# bombhonor.net
KiCad netlist of a schematic drawn in EAGLE
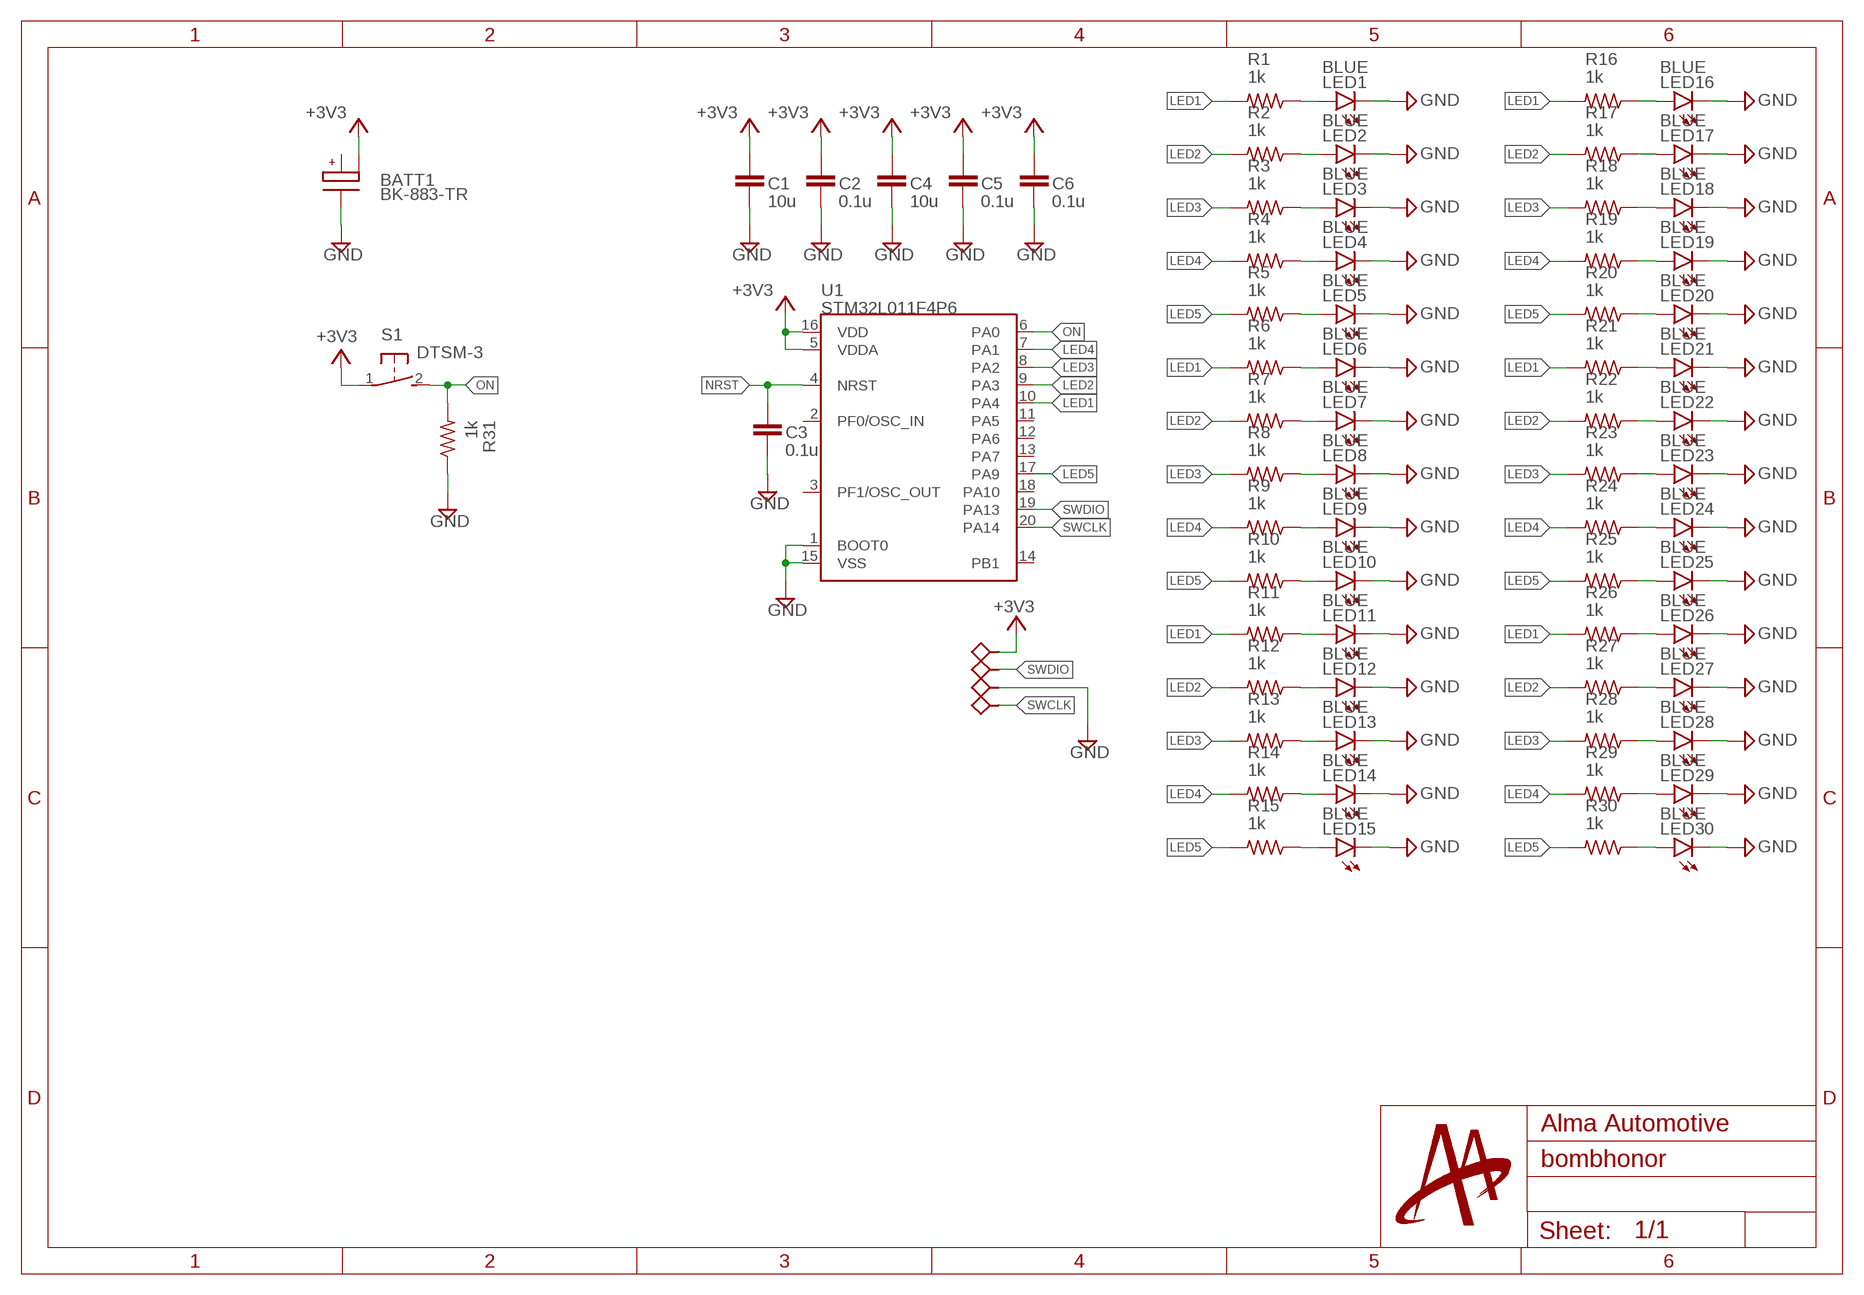
[diagram p0: schematic, sheet 1]

(export (version "E")
  (design (tool "Eeschema 10.0.6"))
  (components
    (comp (ref "BATT1")
      (value "BK-883-TR")
      (footprint "eagle-import:BK-883-TR")
      (libsource (lib "eagle-import") (part "BK-883-TR"))
    )
    (comp (ref "C1")
      (value "10u")
      (footprint "eagle-import:0805[2012]")
      (fields (field (name "PARTNO") "CL21A106KQCLRNC"))
      (libsource (lib "eagle-import") (part "C0805"))
    )
    (comp (ref "C2")
      (value "0.1u")
      (footprint "eagle-import:0603[1608]")
      (fields (field (name "PARTNO") "CL10B104KB8NNNC"))
      (libsource (lib "eagle-import") (part "C0603"))
    )
    (comp (ref "C3")
      (value "0.1u")
      (footprint "eagle-import:0603[1608]")
      (fields (field (name "PARTNO") "CL10B104KB8NNNC"))
      (libsource (lib "eagle-import") (part "C0603"))
    )
    (comp (ref "C4")
      (value "10u")
      (footprint "eagle-import:0805[2012]")
      (fields (field (name "PARTNO") "CL21A106KQCLRNC"))
      (libsource (lib "eagle-import") (part "C0805"))
    )
    (comp (ref "C5")
      (value "0.1u")
      (footprint "eagle-import:0603[1608]")
      (fields (field (name "PARTNO") "CL10B104KB8NNNC"))
      (libsource (lib "eagle-import") (part "C0603"))
    )
    (comp (ref "C6")
      (value "0.1u")
      (footprint "eagle-import:0603[1608]")
      (fields (field (name "PARTNO") "CL10B104KB8NNNC"))
      (libsource (lib "eagle-import") (part "C0603"))
    )
    (comp (ref "LED1")
      (value "BLUE")
      (footprint "eagle-import:1206[3216]BOTTOM_ENTRY")
      (fields (field (name "PARTNO") "LTST-C230TBKT"))
      (libsource (lib "eagle-import") (part "LED_SMD1206"))
    )
    (comp (ref "LED2")
      (value "BLUE")
      (footprint "eagle-import:1206[3216]BOTTOM_ENTRY")
      (fields (field (name "PARTNO") "LTST-C230TBKT"))
      (libsource (lib "eagle-import") (part "LED_SMD1206"))
    )
    (comp (ref "LED3")
      (value "BLUE")
      (footprint "eagle-import:1206[3216]BOTTOM_ENTRY")
      (fields (field (name "PARTNO") "LTST-C230TBKT"))
      (libsource (lib "eagle-import") (part "LED_SMD1206"))
    )
    (comp (ref "LED4")
      (value "BLUE")
      (footprint "eagle-import:1206[3216]BOTTOM_ENTRY")
      (fields (field (name "PARTNO") "LTST-C230TBKT"))
      (libsource (lib "eagle-import") (part "LED_SMD1206"))
    )
    (comp (ref "LED5")
      (value "BLUE")
      (footprint "eagle-import:1206[3216]BOTTOM_ENTRY")
      (fields (field (name "PARTNO") "LTST-C230TBKT"))
      (libsource (lib "eagle-import") (part "LED_SMD1206"))
    )
    (comp (ref "LED6")
      (value "BLUE")
      (footprint "eagle-import:1206[3216]BOTTOM_ENTRY")
      (fields (field (name "PARTNO") "LTST-C230TBKT"))
      (libsource (lib "eagle-import") (part "LED_SMD1206"))
    )
    (comp (ref "LED7")
      (value "BLUE")
      (footprint "eagle-import:1206[3216]BOTTOM_ENTRY")
      (fields (field (name "PARTNO") "LTST-C230TBKT"))
      (libsource (lib "eagle-import") (part "LED_SMD1206"))
    )
    (comp (ref "LED8")
      (value "BLUE")
      (footprint "eagle-import:1206[3216]BOTTOM_ENTRY")
      (fields (field (name "PARTNO") "LTST-C230TBKT"))
      (libsource (lib "eagle-import") (part "LED_SMD1206"))
    )
    (comp (ref "LED9")
      (value "BLUE")
      (footprint "eagle-import:1206[3216]BOTTOM_ENTRY")
      (fields (field (name "PARTNO") "LTST-C230TBKT"))
      (libsource (lib "eagle-import") (part "LED_SMD1206"))
    )
    (comp (ref "LED10")
      (value "BLUE")
      (footprint "eagle-import:1206[3216]BOTTOM_ENTRY")
      (fields (field (name "PARTNO") "LTST-C230TBKT"))
      (libsource (lib "eagle-import") (part "LED_SMD1206"))
    )
    (comp (ref "LED11")
      (value "BLUE")
      (footprint "eagle-import:1206[3216]BOTTOM_ENTRY")
      (fields (field (name "PARTNO") "LTST-C230TBKT"))
      (libsource (lib "eagle-import") (part "LED_SMD1206"))
    )
    (comp (ref "LED12")
      (value "BLUE")
      (footprint "eagle-import:1206[3216]BOTTOM_ENTRY")
      (fields (field (name "PARTNO") "LTST-C230TBKT"))
      (libsource (lib "eagle-import") (part "LED_SMD1206"))
    )
    (comp (ref "LED13")
      (value "BLUE")
      (footprint "eagle-import:1206[3216]BOTTOM_ENTRY")
      (fields (field (name "PARTNO") "LTST-C230TBKT"))
      (libsource (lib "eagle-import") (part "LED_SMD1206"))
    )
    (comp (ref "LED14")
      (value "BLUE")
      (footprint "eagle-import:1206[3216]BOTTOM_ENTRY")
      (fields (field (name "PARTNO") "LTST-C230TBKT"))
      (libsource (lib "eagle-import") (part "LED_SMD1206"))
    )
    (comp (ref "LED15")
      (value "BLUE")
      (footprint "eagle-import:1206[3216]BOTTOM_ENTRY")
      (fields (field (name "PARTNO") "LTST-C230TBKT"))
      (libsource (lib "eagle-import") (part "LED_SMD1206"))
    )
    (comp (ref "LED16")
      (value "BLUE")
      (footprint "eagle-import:1206[3216]BOTTOM_ENTRY")
      (fields (field (name "PARTNO") "LTST-C230TBKT"))
      (libsource (lib "eagle-import") (part "LED_SMD1206"))
    )
    (comp (ref "LED17")
      (value "BLUE")
      (footprint "eagle-import:1206[3216]BOTTOM_ENTRY")
      (fields (field (name "PARTNO") "LTST-C230TBKT"))
      (libsource (lib "eagle-import") (part "LED_SMD1206"))
    )
    (comp (ref "LED18")
      (value "BLUE")
      (footprint "eagle-import:1206[3216]BOTTOM_ENTRY")
      (fields (field (name "PARTNO") "LTST-C230TBKT"))
      (libsource (lib "eagle-import") (part "LED_SMD1206"))
    )
    (comp (ref "LED19")
      (value "BLUE")
      (footprint "eagle-import:1206[3216]BOTTOM_ENTRY")
      (fields (field (name "PARTNO") "LTST-C230TBKT"))
      (libsource (lib "eagle-import") (part "LED_SMD1206"))
    )
    (comp (ref "LED20")
      (value "BLUE")
      (footprint "eagle-import:1206[3216]BOTTOM_ENTRY")
      (fields (field (name "PARTNO") "LTST-C230TBKT"))
      (libsource (lib "eagle-import") (part "LED_SMD1206"))
    )
    (comp (ref "LED21")
      (value "BLUE")
      (footprint "eagle-import:1206[3216]BOTTOM_ENTRY")
      (fields (field (name "PARTNO") "LTST-C230TBKT"))
      (libsource (lib "eagle-import") (part "LED_SMD1206"))
    )
    (comp (ref "LED22")
      (value "BLUE")
      (footprint "eagle-import:1206[3216]BOTTOM_ENTRY")
      (fields (field (name "PARTNO") "LTST-C230TBKT"))
      (libsource (lib "eagle-import") (part "LED_SMD1206"))
    )
    (comp (ref "LED23")
      (value "BLUE")
      (footprint "eagle-import:1206[3216]BOTTOM_ENTRY")
      (fields (field (name "PARTNO") "LTST-C230TBKT"))
      (libsource (lib "eagle-import") (part "LED_SMD1206"))
    )
    (comp (ref "LED24")
      (value "BLUE")
      (footprint "eagle-import:1206[3216]BOTTOM_ENTRY")
      (fields (field (name "PARTNO") "LTST-C230TBKT"))
      (libsource (lib "eagle-import") (part "LED_SMD1206"))
    )
    (comp (ref "LED25")
      (value "BLUE")
      (footprint "eagle-import:1206[3216]BOTTOM_ENTRY")
      (fields (field (name "PARTNO") "LTST-C230TBKT"))
      (libsource (lib "eagle-import") (part "LED_SMD1206"))
    )
    (comp (ref "LED26")
      (value "BLUE")
      (footprint "eagle-import:1206[3216]BOTTOM_ENTRY")
      (fields (field (name "PARTNO") "LTST-C230TBKT"))
      (libsource (lib "eagle-import") (part "LED_SMD1206"))
    )
    (comp (ref "LED27")
      (value "BLUE")
      (footprint "eagle-import:1206[3216]BOTTOM_ENTRY")
      (fields (field (name "PARTNO") "LTST-C230TBKT"))
      (libsource (lib "eagle-import") (part "LED_SMD1206"))
    )
    (comp (ref "LED28")
      (value "BLUE")
      (footprint "eagle-import:1206[3216]BOTTOM_ENTRY")
      (fields (field (name "PARTNO") "LTST-C230TBKT"))
      (libsource (lib "eagle-import") (part "LED_SMD1206"))
    )
    (comp (ref "LED29")
      (value "BLUE")
      (footprint "eagle-import:1206[3216]BOTTOM_ENTRY")
      (fields (field (name "PARTNO") "LTST-C230TBKT"))
      (libsource (lib "eagle-import") (part "LED_SMD1206"))
    )
    (comp (ref "LED30")
      (value "BLUE")
      (footprint "eagle-import:1206[3216]BOTTOM_ENTRY")
      (fields (field (name "PARTNO") "LTST-C230TBKT"))
      (libsource (lib "eagle-import") (part "LED_SMD1206"))
    )
    (comp (ref "R1")
      (value "1k")
      (footprint "eagle-import:0603[1608]")
      (fields (field (name "PARTNO") "RMCF0603JT1K00"))
      (libsource (lib "eagle-import") (part "R0603"))
    )
    (comp (ref "R2")
      (value "1k")
      (footprint "eagle-import:0603[1608]")
      (fields (field (name "PARTNO") "RMCF0603JT1K00"))
      (libsource (lib "eagle-import") (part "R0603"))
    )
    (comp (ref "R3")
      (value "1k")
      (footprint "eagle-import:0603[1608]")
      (fields (field (name "PARTNO") "RMCF0603JT1K00"))
      (libsource (lib "eagle-import") (part "R0603"))
    )
    (comp (ref "R4")
      (value "1k")
      (footprint "eagle-import:0603[1608]")
      (fields (field (name "PARTNO") "RMCF0603JT1K00"))
      (libsource (lib "eagle-import") (part "R0603"))
    )
    (comp (ref "R5")
      (value "1k")
      (footprint "eagle-import:0603[1608]")
      (fields (field (name "PARTNO") "RMCF0603JT1K00"))
      (libsource (lib "eagle-import") (part "R0603"))
    )
    (comp (ref "R6")
      (value "1k")
      (footprint "eagle-import:0603[1608]")
      (fields (field (name "PARTNO") "RMCF0603JT1K00"))
      (libsource (lib "eagle-import") (part "R0603"))
    )
    (comp (ref "R7")
      (value "1k")
      (footprint "eagle-import:0603[1608]")
      (fields (field (name "PARTNO") "RMCF0603JT1K00"))
      (libsource (lib "eagle-import") (part "R0603"))
    )
    (comp (ref "R8")
      (value "1k")
      (footprint "eagle-import:0603[1608]")
      (fields (field (name "PARTNO") "RMCF0603JT1K00"))
      (libsource (lib "eagle-import") (part "R0603"))
    )
    (comp (ref "R9")
      (value "1k")
      (footprint "eagle-import:0603[1608]")
      (fields (field (name "PARTNO") "RMCF0603JT1K00"))
      (libsource (lib "eagle-import") (part "R0603"))
    )
    (comp (ref "R10")
      (value "1k")
      (footprint "eagle-import:0603[1608]")
      (fields (field (name "PARTNO") "RMCF0603JT1K00"))
      (libsource (lib "eagle-import") (part "R0603"))
    )
    (comp (ref "R11")
      (value "1k")
      (footprint "eagle-import:0603[1608]")
      (fields (field (name "PARTNO") "RMCF0603JT1K00"))
      (libsource (lib "eagle-import") (part "R0603"))
    )
    (comp (ref "R12")
      (value "1k")
      (footprint "eagle-import:0603[1608]")
      (fields (field (name "PARTNO") "RMCF0603JT1K00"))
      (libsource (lib "eagle-import") (part "R0603"))
    )
    (comp (ref "R13")
      (value "1k")
      (footprint "eagle-import:0603[1608]")
      (fields (field (name "PARTNO") "RMCF0603JT1K00"))
      (libsource (lib "eagle-import") (part "R0603"))
    )
    (comp (ref "R14")
      (value "1k")
      (footprint "eagle-import:0603[1608]")
      (fields (field (name "PARTNO") "RMCF0603JT1K00"))
      (libsource (lib "eagle-import") (part "R0603"))
    )
    (comp (ref "R15")
      (value "1k")
      (footprint "eagle-import:0603[1608]")
      (fields (field (name "PARTNO") "RMCF0603JT1K00"))
      (libsource (lib "eagle-import") (part "R0603"))
    )
    (comp (ref "R16")
      (value "1k")
      (footprint "eagle-import:0603[1608]")
      (fields (field (name "PARTNO") "RMCF0603JT1K00"))
      (libsource (lib "eagle-import") (part "R0603"))
    )
    (comp (ref "R17")
      (value "1k")
      (footprint "eagle-import:0603[1608]")
      (fields (field (name "PARTNO") "RMCF0603JT1K00"))
      (libsource (lib "eagle-import") (part "R0603"))
    )
    (comp (ref "R18")
      (value "1k")
      (footprint "eagle-import:0603[1608]")
      (fields (field (name "PARTNO") "RMCF0603JT1K00"))
      (libsource (lib "eagle-import") (part "R0603"))
    )
    (comp (ref "R19")
      (value "1k")
      (footprint "eagle-import:0603[1608]")
      (fields (field (name "PARTNO") "RMCF0603JT1K00"))
      (libsource (lib "eagle-import") (part "R0603"))
    )
    (comp (ref "R20")
      (value "1k")
      (footprint "eagle-import:0603[1608]")
      (fields (field (name "PARTNO") "RMCF0603JT1K00"))
      (libsource (lib "eagle-import") (part "R0603"))
    )
    (comp (ref "R21")
      (value "1k")
      (footprint "eagle-import:0603[1608]")
      (fields (field (name "PARTNO") "RMCF0603JT1K00"))
      (libsource (lib "eagle-import") (part "R0603"))
    )
    (comp (ref "R22")
      (value "1k")
      (footprint "eagle-import:0603[1608]")
      (fields (field (name "PARTNO") "RMCF0603JT1K00"))
      (libsource (lib "eagle-import") (part "R0603"))
    )
    (comp (ref "R23")
      (value "1k")
      (footprint "eagle-import:0603[1608]")
      (fields (field (name "PARTNO") "RMCF0603JT1K00"))
      (libsource (lib "eagle-import") (part "R0603"))
    )
    (comp (ref "R24")
      (value "1k")
      (footprint "eagle-import:0603[1608]")
      (fields (field (name "PARTNO") "RMCF0603JT1K00"))
      (libsource (lib "eagle-import") (part "R0603"))
    )
    (comp (ref "R25")
      (value "1k")
      (footprint "eagle-import:0603[1608]")
      (fields (field (name "PARTNO") "RMCF0603JT1K00"))
      (libsource (lib "eagle-import") (part "R0603"))
    )
    (comp (ref "R26")
      (value "1k")
      (footprint "eagle-import:0603[1608]")
      (fields (field (name "PARTNO") "RMCF0603JT1K00"))
      (libsource (lib "eagle-import") (part "R0603"))
    )
    (comp (ref "R27")
      (value "1k")
      (footprint "eagle-import:0603[1608]")
      (fields (field (name "PARTNO") "RMCF0603JT1K00"))
      (libsource (lib "eagle-import") (part "R0603"))
    )
    (comp (ref "R28")
      (value "1k")
      (footprint "eagle-import:0603[1608]")
      (fields (field (name "PARTNO") "RMCF0603JT1K00"))
      (libsource (lib "eagle-import") (part "R0603"))
    )
    (comp (ref "R29")
      (value "1k")
      (footprint "eagle-import:0603[1608]")
      (fields (field (name "PARTNO") "RMCF0603JT1K00"))
      (libsource (lib "eagle-import") (part "R0603"))
    )
    (comp (ref "R30")
      (value "1k")
      (footprint "eagle-import:0603[1608]")
      (fields (field (name "PARTNO") "RMCF0603JT1K00"))
      (libsource (lib "eagle-import") (part "R0603"))
    )
    (comp (ref "R31")
      (value "1k")
      (footprint "eagle-import:0603[1608]")
      (fields (field (name "PARTNO") "RMCF0603JT1K00"))
      (libsource (lib "eagle-import") (part "R0603"))
    )
    (comp (ref "S1")
      (value "DTSM-3")
      (footprint "eagle-import:DTSM-3")
      (libsource (lib "eagle-import") (part "DTSM-3"))
    )
    (comp (ref "TP1")
      (value "TESTPAD2MM")
      (footprint "eagle-import:TP-2MM")
      (fields (field (name "PARTNO") "DNP"))
      (libsource (lib "eagle-import") (part "TESTPAD2MM"))
    )
    (comp (ref "TP2")
      (value "TESTPAD2MM")
      (footprint "eagle-import:TP-2MM")
      (fields (field (name "PARTNO") "DNP"))
      (libsource (lib "eagle-import") (part "TESTPAD2MM"))
    )
    (comp (ref "TP3")
      (value "TESTPAD2MM")
      (footprint "eagle-import:TP-2MM")
      (fields (field (name "PARTNO") "DNP"))
      (libsource (lib "eagle-import") (part "TESTPAD2MM"))
    )
    (comp (ref "TP4")
      (value "TESTPAD2MM")
      (footprint "eagle-import:TP-2MM")
      (fields (field (name "PARTNO") "DNP"))
      (libsource (lib "eagle-import") (part "TESTPAD2MM"))
    )
    (comp (ref "U1")
      (value "STM32L011F4P6")
      (footprint "eagle-import:TSSOP20")
      (libsource (lib "eagle-import") (part "STM32F030F4"))
    )
  )
  (nets
    (net (code "1") (name "+3V3") (class "Default")
      (node (ref "BATT1") (pin "V+2") (pinfunction "V_BATT2_V+2") (pintype "bidirectional"))
      (node (ref "C1") (pin "1") (pinfunction "1_1") (pintype "passive"))
      (node (ref "C2") (pin "1") (pinfunction "1_1") (pintype "passive"))
      (node (ref "C4") (pin "1") (pinfunction "1_1") (pintype "passive"))
      (node (ref "C5") (pin "1") (pinfunction "1_1") (pintype "passive"))
      (node (ref "C6") (pin "1") (pinfunction "1_1") (pintype "passive"))
      (node (ref "S1") (pin "1") (pinfunction "1_1") (pintype "passive"))
      (node (ref "TP1") (pin "TP") (pinfunction "P$1_TP") (pintype "bidirectional"))
      (node (ref "U1") (pin "16") (pinfunction "VDD_16") (pintype "bidirectional"))
      (node (ref "U1") (pin "5") (pinfunction "VDDA_5") (pintype "bidirectional"))
    )
    (net (code "2") (name "GND") (class "Default")
      (node (ref "BATT1") (pin "V-") (pinfunction "GND_V-") (pintype "bidirectional"))
      (node (ref "C1") (pin "2") (pinfunction "2_2") (pintype "passive"))
      (node (ref "C2") (pin "2") (pinfunction "2_2") (pintype "passive"))
      (node (ref "C3") (pin "2") (pinfunction "2_2") (pintype "passive"))
      (node (ref "C4") (pin "2") (pinfunction "2_2") (pintype "passive"))
      (node (ref "C5") (pin "2") (pinfunction "2_2") (pintype "passive"))
      (node (ref "C6") (pin "2") (pinfunction "2_2") (pintype "passive"))
      (node (ref "LED1") (pin "K") (pinfunction "K_K") (pintype "passive"))
      (node (ref "LED10") (pin "K") (pinfunction "K_K") (pintype "passive"))
      (node (ref "LED11") (pin "K") (pinfunction "K_K") (pintype "passive"))
      (node (ref "LED12") (pin "K") (pinfunction "K_K") (pintype "passive"))
      (node (ref "LED13") (pin "K") (pinfunction "K_K") (pintype "passive"))
      (node (ref "LED14") (pin "K") (pinfunction "K_K") (pintype "passive"))
      (node (ref "LED15") (pin "K") (pinfunction "K_K") (pintype "passive"))
      (node (ref "LED16") (pin "K") (pinfunction "K_K") (pintype "passive"))
      (node (ref "LED17") (pin "K") (pinfunction "K_K") (pintype "passive"))
      (node (ref "LED18") (pin "K") (pinfunction "K_K") (pintype "passive"))
      (node (ref "LED19") (pin "K") (pinfunction "K_K") (pintype "passive"))
      (node (ref "LED2") (pin "K") (pinfunction "K_K") (pintype "passive"))
      (node (ref "LED20") (pin "K") (pinfunction "K_K") (pintype "passive"))
      (node (ref "LED21") (pin "K") (pinfunction "K_K") (pintype "passive"))
      (node (ref "LED22") (pin "K") (pinfunction "K_K") (pintype "passive"))
      (node (ref "LED23") (pin "K") (pinfunction "K_K") (pintype "passive"))
      (node (ref "LED24") (pin "K") (pinfunction "K_K") (pintype "passive"))
      (node (ref "LED25") (pin "K") (pinfunction "K_K") (pintype "passive"))
      (node (ref "LED26") (pin "K") (pinfunction "K_K") (pintype "passive"))
      (node (ref "LED27") (pin "K") (pinfunction "K_K") (pintype "passive"))
      (node (ref "LED28") (pin "K") (pinfunction "K_K") (pintype "passive"))
      (node (ref "LED29") (pin "K") (pinfunction "K_K") (pintype "passive"))
      (node (ref "LED3") (pin "K") (pinfunction "K_K") (pintype "passive"))
      (node (ref "LED30") (pin "K") (pinfunction "K_K") (pintype "passive"))
      (node (ref "LED4") (pin "K") (pinfunction "K_K") (pintype "passive"))
      (node (ref "LED5") (pin "K") (pinfunction "K_K") (pintype "passive"))
      (node (ref "LED6") (pin "K") (pinfunction "K_K") (pintype "passive"))
      (node (ref "LED7") (pin "K") (pinfunction "K_K") (pintype "passive"))
      (node (ref "LED8") (pin "K") (pinfunction "K_K") (pintype "passive"))
      (node (ref "LED9") (pin "K") (pinfunction "K_K") (pintype "passive"))
      (node (ref "R31") (pin "1") (pinfunction "1_1") (pintype "passive"))
      (node (ref "TP3") (pin "TP") (pinfunction "P$1_TP") (pintype "bidirectional"))
      (node (ref "U1") (pin "1") (pinfunction "BOOT0_1") (pintype "bidirectional"))
      (node (ref "U1") (pin "15") (pinfunction "VSS_15") (pintype "bidirectional"))
    )
    (net (code "3") (name "LED1") (class "Default")
      (node (ref "R1") (pin "2") (pinfunction "2_2") (pintype "passive"))
      (node (ref "R11") (pin "2") (pinfunction "2_2") (pintype "passive"))
      (node (ref "R16") (pin "2") (pinfunction "2_2") (pintype "passive"))
      (node (ref "R21") (pin "2") (pinfunction "2_2") (pintype "passive"))
      (node (ref "R26") (pin "2") (pinfunction "2_2") (pintype "passive"))
      (node (ref "R6") (pin "2") (pinfunction "2_2") (pintype "passive"))
      (node (ref "U1") (pin "10") (pinfunction "PA4_10") (pintype "bidirectional"))
    )
    (net (code "4") (name "LED2") (class "Default")
      (node (ref "R12") (pin "2") (pinfunction "2_2") (pintype "passive"))
      (node (ref "R17") (pin "2") (pinfunction "2_2") (pintype "passive"))
      (node (ref "R2") (pin "2") (pinfunction "2_2") (pintype "passive"))
      (node (ref "R22") (pin "2") (pinfunction "2_2") (pintype "passive"))
      (node (ref "R27") (pin "2") (pinfunction "2_2") (pintype "passive"))
      (node (ref "R7") (pin "2") (pinfunction "2_2") (pintype "passive"))
      (node (ref "U1") (pin "9") (pinfunction "PA3_9") (pintype "bidirectional"))
    )
    (net (code "5") (name "LED3") (class "Default")
      (node (ref "R13") (pin "2") (pinfunction "2_2") (pintype "passive"))
      (node (ref "R18") (pin "2") (pinfunction "2_2") (pintype "passive"))
      (node (ref "R23") (pin "2") (pinfunction "2_2") (pintype "passive"))
      (node (ref "R28") (pin "2") (pinfunction "2_2") (pintype "passive"))
      (node (ref "R3") (pin "2") (pinfunction "2_2") (pintype "passive"))
      (node (ref "R8") (pin "2") (pinfunction "2_2") (pintype "passive"))
      (node (ref "U1") (pin "8") (pinfunction "PA2_8") (pintype "bidirectional"))
    )
    (net (code "6") (name "LED4") (class "Default")
      (node (ref "R14") (pin "2") (pinfunction "2_2") (pintype "passive"))
      (node (ref "R19") (pin "2") (pinfunction "2_2") (pintype "passive"))
      (node (ref "R24") (pin "2") (pinfunction "2_2") (pintype "passive"))
      (node (ref "R29") (pin "2") (pinfunction "2_2") (pintype "passive"))
      (node (ref "R4") (pin "2") (pinfunction "2_2") (pintype "passive"))
      (node (ref "R9") (pin "2") (pinfunction "2_2") (pintype "passive"))
      (node (ref "U1") (pin "7") (pinfunction "PA1_7") (pintype "bidirectional"))
    )
    (net (code "7") (name "LED5") (class "Default")
      (node (ref "R10") (pin "2") (pinfunction "2_2") (pintype "passive"))
      (node (ref "R15") (pin "2") (pinfunction "2_2") (pintype "passive"))
      (node (ref "R20") (pin "2") (pinfunction "2_2") (pintype "passive"))
      (node (ref "R25") (pin "2") (pinfunction "2_2") (pintype "passive"))
      (node (ref "R30") (pin "2") (pinfunction "2_2") (pintype "passive"))
      (node (ref "R5") (pin "2") (pinfunction "2_2") (pintype "passive"))
      (node (ref "U1") (pin "17") (pinfunction "PA9_17") (pintype "bidirectional"))
    )
    (net (code "8") (name "NRST") (class "Default")
      (node (ref "C3") (pin "1") (pinfunction "1_1") (pintype "passive"))
      (node (ref "U1") (pin "4") (pinfunction "NRST_4") (pintype "bidirectional"))
    )
    (net (code "9") (name "Net-(LED1-PadA)") (class "Default")
      (node (ref "LED1") (pin "A") (pinfunction "A_A") (pintype "passive"))
      (node (ref "R1") (pin "1") (pinfunction "1_1") (pintype "passive"))
    )
    (net (code "10") (name "Net-(LED2-PadA)") (class "Default")
      (node (ref "LED2") (pin "A") (pinfunction "A_A") (pintype "passive"))
      (node (ref "R2") (pin "1") (pinfunction "1_1") (pintype "passive"))
    )
    (net (code "11") (name "Net-(LED3-PadA)") (class "Default")
      (node (ref "LED3") (pin "A") (pinfunction "A_A") (pintype "passive"))
      (node (ref "R3") (pin "1") (pinfunction "1_1") (pintype "passive"))
    )
    (net (code "12") (name "Net-(LED4-PadA)") (class "Default")
      (node (ref "LED4") (pin "A") (pinfunction "A_A") (pintype "passive"))
      (node (ref "R4") (pin "1") (pinfunction "1_1") (pintype "passive"))
    )
    (net (code "13") (name "Net-(LED5-PadA)") (class "Default")
      (node (ref "LED5") (pin "A") (pinfunction "A_A") (pintype "passive"))
      (node (ref "R5") (pin "1") (pinfunction "1_1") (pintype "passive"))
    )
    (net (code "14") (name "Net-(LED6-PadA)") (class "Default")
      (node (ref "LED6") (pin "A") (pinfunction "A_A") (pintype "passive"))
      (node (ref "R6") (pin "1") (pinfunction "1_1") (pintype "passive"))
    )
    (net (code "15") (name "Net-(LED7-PadA)") (class "Default")
      (node (ref "LED7") (pin "A") (pinfunction "A_A") (pintype "passive"))
      (node (ref "R7") (pin "1") (pinfunction "1_1") (pintype "passive"))
    )
    (net (code "16") (name "Net-(LED8-PadA)") (class "Default")
      (node (ref "LED8") (pin "A") (pinfunction "A_A") (pintype "passive"))
      (node (ref "R8") (pin "1") (pinfunction "1_1") (pintype "passive"))
    )
    (net (code "17") (name "Net-(LED9-PadA)") (class "Default")
      (node (ref "LED9") (pin "A") (pinfunction "A_A") (pintype "passive"))
      (node (ref "R9") (pin "1") (pinfunction "1_1") (pintype "passive"))
    )
    (net (code "18") (name "Net-(LED10-PadA)") (class "Default")
      (node (ref "LED10") (pin "A") (pinfunction "A_A") (pintype "passive"))
      (node (ref "R10") (pin "1") (pinfunction "1_1") (pintype "passive"))
    )
    (net (code "19") (name "Net-(LED11-PadA)") (class "Default")
      (node (ref "LED11") (pin "A") (pinfunction "A_A") (pintype "passive"))
      (node (ref "R11") (pin "1") (pinfunction "1_1") (pintype "passive"))
    )
    (net (code "20") (name "Net-(LED12-PadA)") (class "Default")
      (node (ref "LED12") (pin "A") (pinfunction "A_A") (pintype "passive"))
      (node (ref "R12") (pin "1") (pinfunction "1_1") (pintype "passive"))
    )
    (net (code "21") (name "Net-(LED13-PadA)") (class "Default")
      (node (ref "LED13") (pin "A") (pinfunction "A_A") (pintype "passive"))
      (node (ref "R13") (pin "1") (pinfunction "1_1") (pintype "passive"))
    )
    (net (code "22") (name "Net-(LED14-PadA)") (class "Default")
      (node (ref "LED14") (pin "A") (pinfunction "A_A") (pintype "passive"))
      (node (ref "R14") (pin "1") (pinfunction "1_1") (pintype "passive"))
    )
    (net (code "23") (name "Net-(LED15-PadA)") (class "Default")
      (node (ref "LED15") (pin "A") (pinfunction "A_A") (pintype "passive"))
      (node (ref "R15") (pin "1") (pinfunction "1_1") (pintype "passive"))
    )
    (net (code "24") (name "Net-(LED16-PadA)") (class "Default")
      (node (ref "LED16") (pin "A") (pinfunction "A_A") (pintype "passive"))
      (node (ref "R16") (pin "1") (pinfunction "1_1") (pintype "passive"))
    )
    (net (code "25") (name "Net-(LED17-PadA)") (class "Default")
      (node (ref "LED17") (pin "A") (pinfunction "A_A") (pintype "passive"))
      (node (ref "R17") (pin "1") (pinfunction "1_1") (pintype "passive"))
    )
    (net (code "26") (name "Net-(LED18-PadA)") (class "Default")
      (node (ref "LED18") (pin "A") (pinfunction "A_A") (pintype "passive"))
      (node (ref "R18") (pin "1") (pinfunction "1_1") (pintype "passive"))
    )
    (net (code "27") (name "Net-(LED19-PadA)") (class "Default")
      (node (ref "LED19") (pin "A") (pinfunction "A_A") (pintype "passive"))
      (node (ref "R19") (pin "1") (pinfunction "1_1") (pintype "passive"))
    )
    (net (code "28") (name "Net-(LED20-PadA)") (class "Default")
      (node (ref "LED20") (pin "A") (pinfunction "A_A") (pintype "passive"))
      (node (ref "R20") (pin "1") (pinfunction "1_1") (pintype "passive"))
    )
    (net (code "29") (name "Net-(LED21-PadA)") (class "Default")
      (node (ref "LED21") (pin "A") (pinfunction "A_A") (pintype "passive"))
      (node (ref "R21") (pin "1") (pinfunction "1_1") (pintype "passive"))
    )
    (net (code "30") (name "Net-(LED22-PadA)") (class "Default")
      (node (ref "LED22") (pin "A") (pinfunction "A_A") (pintype "passive"))
      (node (ref "R22") (pin "1") (pinfunction "1_1") (pintype "passive"))
    )
    (net (code "31") (name "Net-(LED23-PadA)") (class "Default")
      (node (ref "LED23") (pin "A") (pinfunction "A_A") (pintype "passive"))
      (node (ref "R23") (pin "1") (pinfunction "1_1") (pintype "passive"))
    )
    (net (code "32") (name "Net-(LED24-PadA)") (class "Default")
      (node (ref "LED24") (pin "A") (pinfunction "A_A") (pintype "passive"))
      (node (ref "R24") (pin "1") (pinfunction "1_1") (pintype "passive"))
    )
    (net (code "33") (name "Net-(LED25-PadA)") (class "Default")
      (node (ref "LED25") (pin "A") (pinfunction "A_A") (pintype "passive"))
      (node (ref "R25") (pin "1") (pinfunction "1_1") (pintype "passive"))
    )
    (net (code "34") (name "Net-(LED26-PadA)") (class "Default")
      (node (ref "LED26") (pin "A") (pinfunction "A_A") (pintype "passive"))
      (node (ref "R26") (pin "1") (pinfunction "1_1") (pintype "passive"))
    )
    (net (code "35") (name "Net-(LED27-PadA)") (class "Default")
      (node (ref "LED27") (pin "A") (pinfunction "A_A") (pintype "passive"))
      (node (ref "R27") (pin "1") (pinfunction "1_1") (pintype "passive"))
    )
    (net (code "36") (name "Net-(LED28-PadA)") (class "Default")
      (node (ref "LED28") (pin "A") (pinfunction "A_A") (pintype "passive"))
      (node (ref "R28") (pin "1") (pinfunction "1_1") (pintype "passive"))
    )
    (net (code "37") (name "Net-(LED29-PadA)") (class "Default")
      (node (ref "LED29") (pin "A") (pinfunction "A_A") (pintype "passive"))
      (node (ref "R29") (pin "1") (pinfunction "1_1") (pintype "passive"))
    )
    (net (code "38") (name "Net-(LED30-PadA)") (class "Default")
      (node (ref "LED30") (pin "A") (pinfunction "A_A") (pintype "passive"))
      (node (ref "R30") (pin "1") (pinfunction "1_1") (pintype "passive"))
    )
    (net (code "39") (name "ON") (class "Default")
      (node (ref "R31") (pin "2") (pinfunction "2_2") (pintype "passive"))
      (node (ref "S1") (pin "2") (pinfunction "2_2") (pintype "passive"))
      (node (ref "U1") (pin "6") (pinfunction "PA0_6") (pintype "bidirectional"))
    )
    (net (code "40") (name "SWCLK") (class "Default")
      (node (ref "TP4") (pin "TP") (pinfunction "P$1_TP") (pintype "bidirectional"))
      (node (ref "U1") (pin "20") (pinfunction "PA14_20") (pintype "bidirectional"))
    )
    (net (code "41") (name "SWDIO") (class "Default")
      (node (ref "TP2") (pin "TP") (pinfunction "P$1_TP") (pintype "bidirectional"))
      (node (ref "U1") (pin "19") (pinfunction "PA13_19") (pintype "bidirectional"))
    )
    (net (code "42") (name "unconnected-(BATT1-V_BATT1-PadV+1)") (class "Default")
      (node (ref "BATT1") (pin "V+1") (pinfunction "V_BATT1_V+1") (pintype "bidirectional"))
    )
    (net (code "43") (name "unconnected-(U1-PA5-Pad11)") (class "Default")
      (node (ref "U1") (pin "11") (pinfunction "PA5_11") (pintype "bidirectional"))
    )
    (net (code "44") (name "unconnected-(U1-PA6-Pad12)") (class "Default")
      (node (ref "U1") (pin "12") (pinfunction "PA6_12") (pintype "bidirectional"))
    )
    (net (code "45") (name "unconnected-(U1-PA7-Pad13)") (class "Default")
      (node (ref "U1") (pin "13") (pinfunction "PA7_13") (pintype "bidirectional"))
    )
    (net (code "46") (name "unconnected-(U1-PA10-Pad18)") (class "Default")
      (node (ref "U1") (pin "18") (pinfunction "PA10_18") (pintype "bidirectional"))
    )
    (net (code "47") (name "unconnected-(U1-PB1-Pad14)") (class "Default")
      (node (ref "U1") (pin "14") (pinfunction "PB1_14") (pintype "bidirectional"))
    )
    (net (code "48") (name "unconnected-(U1-PF0{slash}OSC_IN-Pad2)") (class "Default")
      (node (ref "U1") (pin "2") (pinfunction "PF0/OSC_IN_2") (pintype "bidirectional"))
    )
    (net (code "49") (name "unconnected-(U1-PF1{slash}OSC_OUT-Pad3)") (class "Default")
      (node (ref "U1") (pin "3") (pinfunction "PF1/OSC_OUT_3") (pintype "bidirectional"))
    )
  )
)
